# PID.net
KiCad netlist of a schematic drawn in EasyEDA Pro
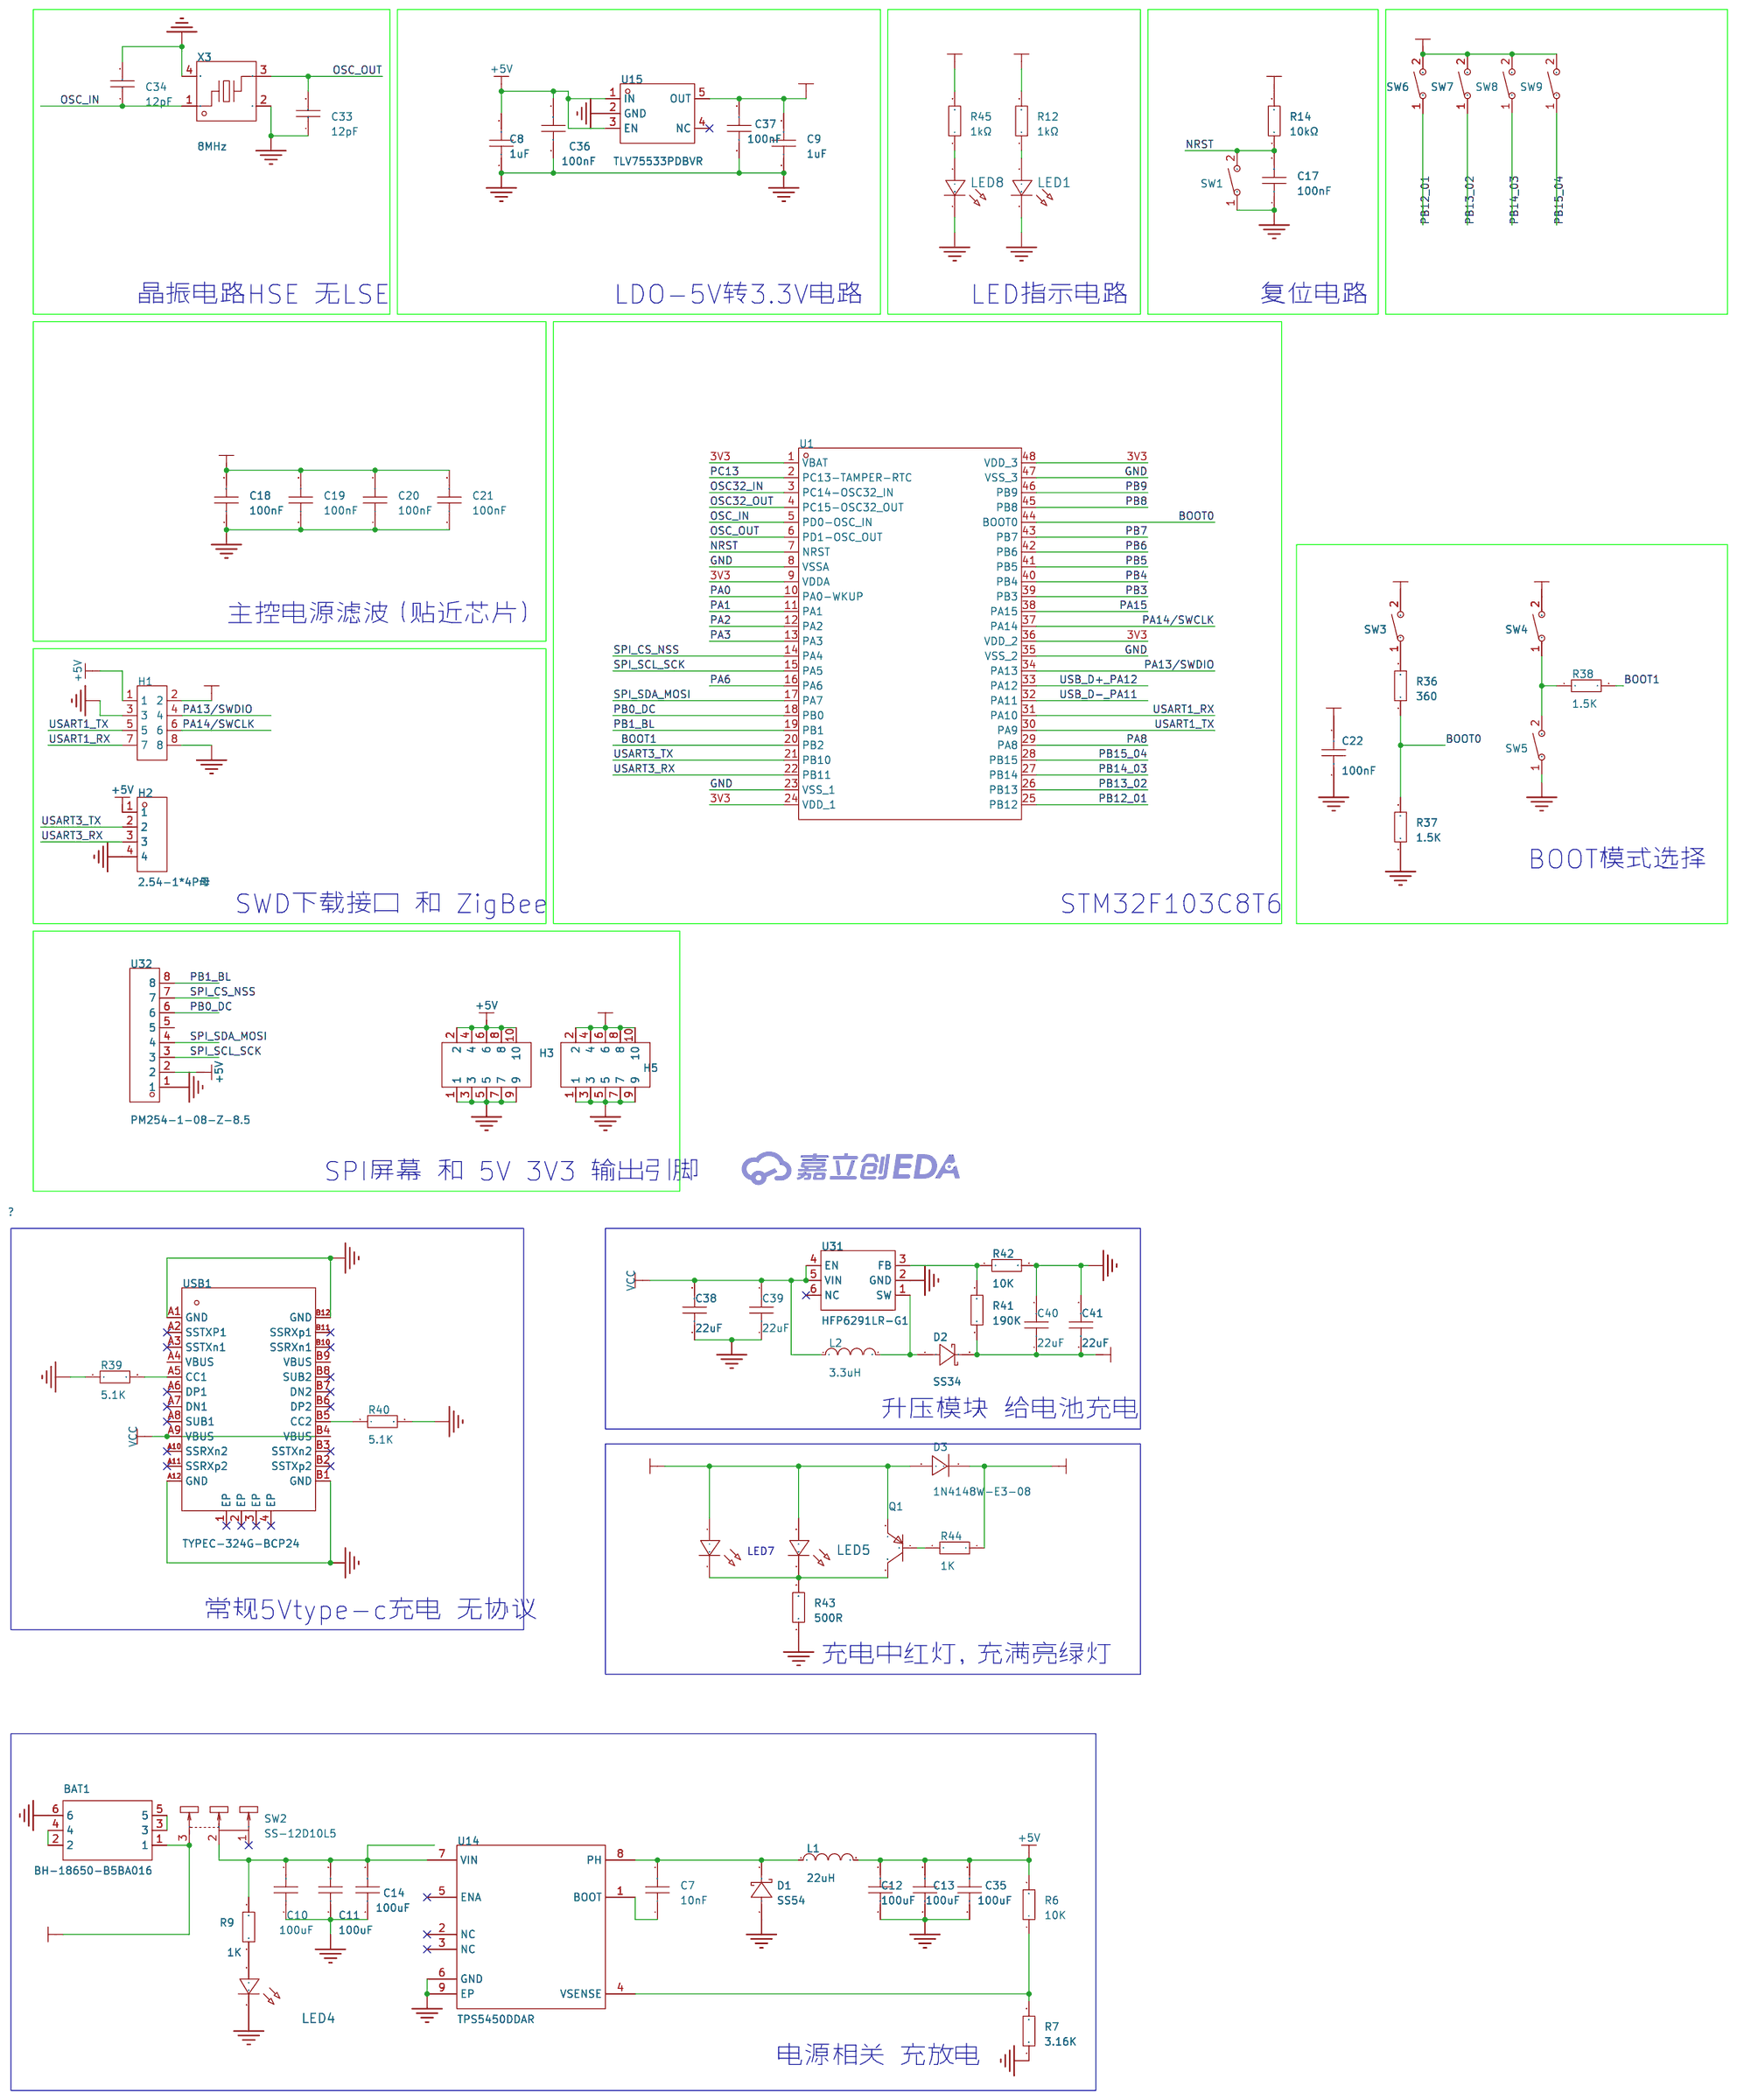
[diagram p0: schematic sheet]

(export (version "E")
  (design (tool "Eeschema 10.0.6"))
  (components
    (comp (ref "BAT1")
      (value "BH-18650-B5BA016")
      (footprint "easyedapro:BAT-SMD_BH-18650-B5BA016")
      (description "连接器类型:电池盒;适用电池规格:-;触点电镀:金;工作温度范围:-25°C~+85°C;")
      (fields (field (name "Manufacturer") "MYOUNG(美阳)"))
      (libsource (lib "easyedapro") (part "BH-18650-B5BA016"))
    )
    (comp (ref "C7")
      (value "100nF")
      (footprint "easyedapro:C0603")
      (libsource (lib "easyedapro") (part "CapAcitance"))
    )
    (comp (ref "C8")
      (value "100nF")
      (footprint "easyedapro:C0603")
      (libsource (lib "easyedapro") (part "CapAcitance"))
    )
    (comp (ref "C9")
      (value "100nF")
      (footprint "easyedapro:C0603")
      (libsource (lib "easyedapro") (part "CapAcitance"))
    )
    (comp (ref "C10")
      (value "100uF")
      (footprint "easyedapro:C1206")
      (description "容值:100uF;精度:±20%;额定电压:10V;材质(温度系数):X5R;")
      (fields
        (field (name "Manufacturer Part") "HGC1206R5107M100NSPJ")
        (field (name "Manufacturer") "Chinocera(华瓷)")
      )
      (libsource (lib "easyedapro") (part "HGC1206R5107M100NSPJ"))
    )
    (comp (ref "C11")
      (value "100uF")
      (footprint "easyedapro:C1206")
      (description "容值:100uF;精度:±20%;额定电压:10V;材质(温度系数):X5R;")
      (fields
        (field (name "Manufacturer Part") "HGC1206R5107M100NSPJ")
        (field (name "Manufacturer") "Chinocera(华瓷)")
      )
      (libsource (lib "easyedapro") (part "HGC1206R5107M100NSPJ"))
    )
    (comp (ref "C12")
      (value "100uF")
      (footprint "easyedapro:C1206")
      (description "容值:100uF;精度:±20%;额定电压:10V;材质(温度系数):X5R;")
      (fields
        (field (name "Manufacturer Part") "HGC1206R5107M100NSPJ")
        (field (name "Manufacturer") "Chinocera(华瓷)")
      )
      (libsource (lib "easyedapro") (part "HGC1206R5107M100NSPJ"))
    )
    (comp (ref "C13")
      (value "100uF")
      (footprint "easyedapro:C1206")
      (description "容值:100uF;精度:±20%;额定电压:10V;材质(温度系数):X5R;")
      (fields
        (field (name "Manufacturer Part") "HGC1206R5107M100NSPJ")
        (field (name "Manufacturer") "Chinocera(华瓷)")
      )
      (libsource (lib "easyedapro") (part "HGC1206R5107M100NSPJ"))
    )
    (comp (ref "C14")
      (value "100uF")
      (footprint "easyedapro:C1206")
      (description "容值:100uF;精度:±20%;额定电压:10V;材质(温度系数):X5R;")
      (fields
        (field (name "Manufacturer Part") "HGC1206R5107M100NSPJ")
        (field (name "Manufacturer") "Chinocera(华瓷)")
      )
      (libsource (lib "easyedapro") (part "HGC1206R5107M100NSPJ"))
    )
    (comp (ref "C17")
      (value "100nF")
      (footprint "easyedapro:C0402")
      (description "容值:100nF;精度:±10%;额定电压:50V;材质(温度系数):X7R;")
      (fields
        (field (name "Manufacturer Part") "GRM155R71H104KE14D")
        (field (name "Manufacturer") "muRata(村田)")
      )
      (libsource (lib "easyedapro") (part "GRM155R71H104KE14D"))
    )
    (comp (ref "C18")
      (value "100nF")
      (footprint "easyedapro:C0402")
      (description "容值:100nF;精度:±10%;额定电压:50V;材质(温度系数):X7R;")
      (fields
        (field (name "Manufacturer Part") "GRM155R71H104KE14D")
        (field (name "Manufacturer") "muRata(村田)")
      )
      (libsource (lib "easyedapro") (part "GRM155R71H104KE14D"))
    )
    (comp (ref "C19")
      (value "100nF")
      (footprint "easyedapro:C0402")
      (description "容值:100nF;精度:±10%;额定电压:50V;材质(温度系数):X7R;")
      (fields
        (field (name "Manufacturer Part") "GRM155R71H104KE14D")
        (field (name "Manufacturer") "muRata(村田)")
      )
      (libsource (lib "easyedapro") (part "GRM155R71H104KE14D"))
    )
    (comp (ref "C20")
      (value "100nF")
      (footprint "easyedapro:C0402")
      (description "容值:100nF;精度:±10%;额定电压:50V;材质(温度系数):X7R;")
      (fields
        (field (name "Manufacturer Part") "GRM155R71H104KE14D")
        (field (name "Manufacturer") "muRata(村田)")
      )
      (libsource (lib "easyedapro") (part "GRM155R71H104KE14D"))
    )
    (comp (ref "C21")
      (value "100nF")
      (footprint "easyedapro:C0402")
      (description "容值:100nF;精度:±10%;额定电压:50V;材质(温度系数):X7R;")
      (fields
        (field (name "Manufacturer Part") "GRM155R71H104KE14D")
        (field (name "Manufacturer") "muRata(村田)")
      )
      (libsource (lib "easyedapro") (part "GRM155R71H104KE14D"))
    )
    (comp (ref "C22")
      (value "100nF")
      (footprint "easyedapro:C0402")
      (description "容值:100nF;精度:±10%;额定电压:50V;材质(温度系数):X7R;")
      (fields
        (field (name "Manufacturer Part") "GRM155R71H104KE14D")
        (field (name "Manufacturer") "muRata(村田)")
      )
      (libsource (lib "easyedapro") (part "GRM155R71H104KE14D"))
    )
    (comp (ref "C33")
      (value "12pF")
      (footprint "easyedapro:C0402")
      (description "容值:12pF;精度:±5%;额定电压:50V;材质(温度系数):C0G;")
      (fields (field (name "Manufacturer Part") "0402CG120J500NT") (field (name "Manufacturer") "FH(风华)"))
      (libsource (lib "easyedapro") (part "0402CG120J500NT"))
    )
    (comp (ref "C34")
      (value "12pF")
      (footprint "easyedapro:C0402")
      (description "容值:12pF;精度:±5%;额定电压:50V;材质(温度系数):C0G;")
      (fields (field (name "Manufacturer Part") "0402CG120J500NT") (field (name "Manufacturer") "FH(风华)"))
      (libsource (lib "easyedapro") (part "0402CG120J500NT"))
    )
    (comp (ref "C35")
      (value "100uF")
      (footprint "easyedapro:C1206")
      (description "容值:100uF;精度:±20%;额定电压:10V;材质(温度系数):X5R;")
      (fields
        (field (name "Manufacturer Part") "HGC1206R5107M100NSPJ")
        (field (name "Manufacturer") "Chinocera(华瓷)")
      )
      (libsource (lib "easyedapro") (part "HGC1206R5107M100NSPJ"))
    )
    (comp (ref "C36")
      (value "100nF")
      (footprint "easyedapro:C0402")
      (description "容值:100nF;精度:±10%;额定电压:50V;材质(温度系数):X7R;")
      (fields
        (field (name "Manufacturer Part") "GRM155R71H104KE14D")
        (field (name "Manufacturer") "muRata(村田)")
      )
      (libsource (lib "easyedapro") (part "GRM155R71H104KE14D"))
    )
    (comp (ref "C37")
      (value "100nF")
      (footprint "easyedapro:C0402")
      (description "容值:100nF;精度:±10%;额定电压:50V;材质(温度系数):X7R;")
      (fields
        (field (name "Manufacturer Part") "GRM155R71H104KE14D")
        (field (name "Manufacturer") "muRata(村田)")
      )
      (libsource (lib "easyedapro") (part "GRM155R71H104KE14D"))
    )
    (comp (ref "C38")
      (value "22uF")
      (footprint "easyedapro:C0603")
      (libsource (lib "easyedapro") (part "CapAcitance"))
    )
    (comp (ref "C39")
      (value "22uF")
      (footprint "easyedapro:C0603")
      (libsource (lib "easyedapro") (part "CapAcitance"))
    )
    (comp (ref "C40")
      (value "22uF")
      (footprint "easyedapro:C0603")
      (libsource (lib "easyedapro") (part "CapAcitance"))
    )
    (comp (ref "C41")
      (value "22uF")
      (footprint "easyedapro:C0603")
      (libsource (lib "easyedapro") (part "CapAcitance"))
    )
    (comp (ref "D1")
      (value "SS54")
      (footprint "easyedapro:SMA_L4.3-W2.6-LS5.0-FD")
      (description "二极管配置:独立式;正向压降(Vf):550mV@5.0A;直流反向耐压(Vr):40V;整流电流:5A;")
      (fields (field (name "Manufacturer") "宏迦橙"))
      (libsource (lib "easyedapro") (part "SS54_C7420369"))
    )
    (comp (ref "D2")
      (value "SS34")
      (footprint "easyedapro:SMA_L4.3-W2.6-LS5.0-FD")
      (description "二极管配置:独立式;正向压降(Vf):550mV@3.0A;直流反向耐压(Vr):40V;整流电流:3A;")
      (fields (field (name "Manufacturer") "宏嘉诚"))
      (libsource (lib "easyedapro") (part "SS34_C7420365"))
    )
    (comp (ref "D3")
      (value "1N4148W-E3-08")
      (footprint "easyedapro:SOD-123_L2.8-W1.8-LS3.7-RD")
      (description "二极管配置:1个独立式;正向压降(Vf):1.2V@100mA;直流反向耐压(Vr):75V;整流电流:150mA;反向恢复时间(Trr):4ns;")
      (fields (field (name "Manufacturer") "VISHAY(威世)"))
      (libsource (lib "easyedapro") (part "1N4148W-E3-08"))
    )
    (comp (ref "H1")
      (value "HX PZ2.54-4x2P ZZ")
      (footprint "easyedapro:HDR-TH_8P-P2.54-V-M-R2-C4-S2.54")
      (fields (field (name "Manufacturer") "hanxia(韩下)"))
      (libsource (lib "easyedapro") (part "HX PZ2.54-4X2P ZZ"))
    )
    (comp (ref "H2")
      (value "2.54-1*4P母")
      (footprint "easyedapro:HDR-TH_4P-P2.54-V-F")
      (fields (field (name "Manufacturer") "BOOMELE(博穆精密)"))
      (libsource (lib "easyedapro") (part "2.54-1*4P母"))
    )
    (comp (ref "H3")
      (value "PZ254V-12-10P")
      (footprint "easyedapro:HDR-TH_10P-P2.54-V-M-R2-C5-S2.54")
      (fields (field (name "Manufacturer") "XFCN(兴飞)"))
      (libsource (lib "easyedapro") (part "PZ254V-12-10P"))
    )
    (comp (ref "H5")
      (value "PZ254V-12-10P")
      (footprint "easyedapro:HDR-TH_10P-P2.54-V-M-R2-C5-S2.54")
      (fields (field (name "Manufacturer") "XFCN(兴飞)"))
      (libsource (lib "easyedapro") (part "PZ254V-12-10P"))
    )
    (comp (ref "L1")
      (value "22uH")
      (footprint "easyedapro:IND-SMD_L7.1-W6.6")
      (description "电感值:22uH;精度:±20%;额定电流:3A;")
      (fields
        (field (name "Manufacturer Part") "YSPI0630A-220M")
        (field (name "Manufacturer") "YJYCOIN(益嘉源)")
      )
      (libsource (lib "easyedapro") (part "YSPI0630A-220M"))
    )
    (comp (ref "L2")
      (value "3.3uH")
      (footprint "easyedapro:IND-SMD_L4.4-W4.2-A")
      (description "电感值:3.3uH;精度:±20%;额定电流:3.3A;饱和电流(Isat):4A;类型:一体成型电感;")
      (fields (field (name "Manufacturer Part") "FXL0420-3R3-M") (field (name "Manufacturer") "cjiang(长江微电)"))
      (libsource (lib "easyedapro") (part "FXL0420-3R3-M"))
    )
    (comp (ref "LED1")
      (value "LTST-C190KSKT")
      (footprint "easyedapro:LED_0603")
      (fields (field (name "Manufacturer") "LITEON(光宝)"))
      (libsource (lib "easyedapro") (part "LED_R"))
    )
    (comp (ref "LED4")
      (value "~")
      (footprint "easyedapro:LED_0603")
      (libsource (lib "easyedapro") (part "LED_R"))
    )
    (comp (ref "LED5")
      (value "~")
      (footprint "easyedapro:LED_0603")
      (libsource (lib "easyedapro") (part "LED_R"))
    )
    (comp (ref "LED7")
      (value "~")
      (footprint "easyedapro:LED_0603")
      (libsource (lib "easyedapro") (part "LED_G"))
    )
    (comp (ref "LED8")
      (value "LTST-C190KSKT")
      (footprint "easyedapro:LED_0603")
      (fields (field (name "Manufacturer") "LITEON(光宝)"))
      (libsource (lib "easyedapro") (part "LED_R"))
    )
    (comp (ref "Q1")
      (value "~")
      (footprint "easyedapro:S8550P_SOT")
      (libsource (lib "easyedapro") (part "PNP"))
    )
    (comp (ref "R6") (value "10K") (footprint "easyedapro:R0603") (libsource (lib "easyedapro") (part "电阻")))
    (comp (ref "R7") (value "10K") (footprint "easyedapro:R0603") (libsource (lib "easyedapro") (part "电阻")))
    (comp (ref "R9") (value "1K") (footprint "easyedapro:R0603") (libsource (lib "easyedapro") (part "电阻")))
    (comp (ref "R12")
      (value "1kΩ")
      (footprint "easyedapro:R0402")
      (description "电阻类型:厚膜电阻;阻值:1kΩ;精度:±1%;功率:62.5mW;最大工作电压:50V;温度系数:±100ppm/°C;")
      (fields
        (field (name "Manufacturer Part") "0402WGF1001TCE")
        (field (name "Manufacturer") "UNI-ROYAL(厚声)")
      )
      (libsource (lib "easyedapro") (part "0402WGF1001TCE"))
    )
    (comp (ref "R14")
      (value "10kΩ")
      (footprint "easyedapro:R0402")
      (description "电阻类型:厚膜电阻;阻值:10kΩ;精度:±1%;功率:62.5mW;最大工作电压:50V;温度系数:±100ppm/°C;")
      (fields (field (name "Manufacturer Part") "RC0402FR-0710KL") (field (name "Manufacturer") "YAGEO(国巨)"))
      (libsource (lib "easyedapro") (part "RC0402FR-0710KL"))
    )
    (comp (ref "R36") (value "360") (footprint "easyedapro:R0603") (libsource (lib "easyedapro") (part "电阻")))
    (comp (ref "R37")
      (value "1.5K")
      (footprint "easyedapro:R0603")
      (libsource (lib "easyedapro") (part "电阻"))
    )
    (comp (ref "R38")
      (value "1.5K")
      (footprint "easyedapro:R0603")
      (libsource (lib "easyedapro") (part "电阻"))
    )
    (comp (ref "R39")
      (value "5.1K")
      (footprint "easyedapro:R0603")
      (libsource (lib "easyedapro") (part "电阻"))
    )
    (comp (ref "R40")
      (value "5.1K")
      (footprint "easyedapro:R0603")
      (libsource (lib "easyedapro") (part "电阻"))
    )
    (comp (ref "R41")
      (value "190K")
      (footprint "easyedapro:R0603")
      (libsource (lib "easyedapro") (part "电阻"))
    )
    (comp (ref "R42") (value "10K") (footprint "easyedapro:R0603") (libsource (lib "easyedapro") (part "电阻")))
    (comp (ref "R43")
      (value "500R")
      (footprint "easyedapro:R0603")
      (libsource (lib "easyedapro") (part "电阻"))
    )
    (comp (ref "R44") (value "1K") (footprint "easyedapro:R0603") (libsource (lib "easyedapro") (part "电阻")))
    (comp (ref "R45")
      (value "1kΩ")
      (footprint "easyedapro:R0402")
      (description "电阻类型:厚膜电阻;阻值:1kΩ;精度:±1%;功率:62.5mW;最大工作电压:50V;温度系数:±100ppm/°C;")
      (fields
        (field (name "Manufacturer Part") "0402WGF1001TCE")
        (field (name "Manufacturer") "UNI-ROYAL(厚声)")
      )
      (libsource (lib "easyedapro") (part "0402WGF1001TCE"))
    )
    (comp (ref "SW1")
      (value "TS-1101-B-W")
      (footprint "easyedapro:KEY-SMD_2P-L6.0-W3.6-P7.4-LS8.0-L")
      (description "触点电流:50mA;额定电压(DC):12V;绝缘电阻:-;电路结构:单刀单掷;安装方式:立贴;带灯:无;作用力:160gf;机械寿命:5万次;带支架:否;")
      (fields (field (name "Manufacturer") "XKB Connectivity(中国星坤)"))
      (libsource (lib "easyedapro") (part "TS-1101-B-W"))
    )
    (comp (ref "SW2")
      (value "SS-12D10L5")
      (footprint "easyedapro:SW-TH_SS-12D10L5")
      (description "电路结构:单刀双掷;安装方式:直插;开关颜色:黑色;额定电流(DC):3A;额定电压(DC):125V;额定电流(AC):3A;额定电压(AC):125V;机械寿命:1万次;")
      (fields (field (name "Manufacturer") "XKB Connectivity(中国星坤)"))
      (libsource (lib "easyedapro") (part "SS-12D10L5"))
    )
    (comp (ref "SW3")
      (value "TS-1101-B-W")
      (footprint "easyedapro:KEY-SMD_2P-L6.0-W3.6-P7.4-LS8.0-L")
      (description "触点电流:50mA;额定电压(DC):12V;绝缘电阻:-;电路结构:单刀单掷;安装方式:立贴;带灯:无;作用力:160gf;机械寿命:5万次;带支架:否;")
      (fields (field (name "Manufacturer") "XKB Connectivity(中国星坤)"))
      (libsource (lib "easyedapro") (part "TS-1101-B-W"))
    )
    (comp (ref "SW4")
      (value "TS-1101-B-W")
      (footprint "easyedapro:KEY-SMD_2P-L6.0-W3.6-P7.4-LS8.0-L")
      (description "触点电流:50mA;额定电压(DC):12V;绝缘电阻:-;电路结构:单刀单掷;安装方式:立贴;带灯:无;作用力:160gf;机械寿命:5万次;带支架:否;")
      (fields (field (name "Manufacturer") "XKB Connectivity(中国星坤)"))
      (libsource (lib "easyedapro") (part "TS-1101-B-W"))
    )
    (comp (ref "SW5")
      (value "TS-1101-B-W")
      (footprint "easyedapro:KEY-SMD_2P-L6.0-W3.6-P7.4-LS8.0-L")
      (description "触点电流:50mA;额定电压(DC):12V;绝缘电阻:-;电路结构:单刀单掷;安装方式:立贴;带灯:无;作用力:160gf;机械寿命:5万次;带支架:否;")
      (fields (field (name "Manufacturer") "XKB Connectivity(中国星坤)"))
      (libsource (lib "easyedapro") (part "TS-1101-B-W"))
    )
    (comp (ref "SW6")
      (value "TS-1101-B-W")
      (footprint "easyedapro:KEY-SMD_2P-L6.0-W3.6-P7.4-LS8.0-L")
      (description "触点电流:50mA;额定电压(DC):12V;绝缘电阻:-;电路结构:单刀单掷;安装方式:立贴;带灯:无;作用力:160gf;机械寿命:5万次;带支架:否;")
      (fields (field (name "Manufacturer") "XKB Connectivity(中国星坤)"))
      (libsource (lib "easyedapro") (part "TS-1101-B-W"))
    )
    (comp (ref "SW7")
      (value "TS-1101-B-W")
      (footprint "easyedapro:KEY-SMD_2P-L6.0-W3.6-P7.4-LS8.0-L")
      (description "触点电流:50mA;额定电压(DC):12V;绝缘电阻:-;电路结构:单刀单掷;安装方式:立贴;带灯:无;作用力:160gf;机械寿命:5万次;带支架:否;")
      (fields (field (name "Manufacturer") "XKB Connectivity(中国星坤)"))
      (libsource (lib "easyedapro") (part "TS-1101-B-W"))
    )
    (comp (ref "SW8")
      (value "TS-1101-B-W")
      (footprint "easyedapro:KEY-SMD_2P-L6.0-W3.6-P7.4-LS8.0-L")
      (description "触点电流:50mA;额定电压(DC):12V;绝缘电阻:-;电路结构:单刀单掷;安装方式:立贴;带灯:无;作用力:160gf;机械寿命:5万次;带支架:否;")
      (fields (field (name "Manufacturer") "XKB Connectivity(中国星坤)"))
      (libsource (lib "easyedapro") (part "TS-1101-B-W"))
    )
    (comp (ref "SW9")
      (value "TS-1101-B-W")
      (footprint "easyedapro:KEY-SMD_2P-L6.0-W3.6-P7.4-LS8.0-L")
      (description "触点电流:50mA;额定电压(DC):12V;绝缘电阻:-;电路结构:单刀单掷;安装方式:立贴;带灯:无;作用力:160gf;机械寿命:5万次;带支架:否;")
      (fields (field (name "Manufacturer") "XKB Connectivity(中国星坤)"))
      (libsource (lib "easyedapro") (part "TS-1101-B-W"))
    )
    (comp (ref "U1")
      (value "STM32F103C8T6")
      (footprint "easyedapro:LQFP-48_L7.0-W7.0-P0.50-LS9.0-BL")
      (description "CPU内核:CM3;程序存储容量:64KB;RAM总容量:20KB;GPIO端口数量:37;工作电压范围:2V~3.6V;CPU最大主频:72MHz;程序存储器类型:FLASH;")
      (fields (field (name "Manufacturer") "ST(意法半导体)"))
      (libsource (lib "easyedapro") (part "STM32F103C8T6"))
    )
    (comp (ref "U14")
      (value "TPS5450DDAR")
      (footprint "easyedapro:SOP-8_L4.9-W3.9-P1.27-LS6.0-BL-EP")
      (description "功能类型:降压型;输出类型:可调;工作电压:5.5V~36V;输出电压:1.221V~31.32V;输出电流:5A;")
      (fields (field (name "Manufacturer") "TI(德州仪器)"))
      (libsource (lib "easyedapro") (part "TPS5450DDAR"))
    )
    (comp (ref "U15")
      (value "TLV75533PDBVR")
      (footprint "easyedapro:SOT-23-5_L3.0-W1.7-P0.95-LS2.8-BR")
      (description "输出类型:固定;最大输入电压:5.5V;输出电压:3.3V;输出电流:500mA;电源纹波抑制比(PSRR):52dB;输出极性:正极;")
      (fields (field (name "Manufacturer") "TI(德州仪器)"))
      (libsource (lib "easyedapro") (part "TLV75533PDBVR"))
    )
    (comp (ref "U31")
      (value "HFP6291LR-G1")
      (footprint "easyedapro:SOT-23-6_L2.9-W1.6-P0.95-LS2.8-BR")
      (description "功能类型:升压型;输出类型:-;工作电压:2V~24V;输出电压:-;输出电流:-;")
      (fields (field (name "Manufacturer") "HXY MOSFET(华轩阳电子)"))
      (libsource (lib "easyedapro") (part "HFP6291LR-G1"))
    )
    (comp (ref "U32")
      (value "PM254-1-08-Z-8.5")
      (footprint "easyedapro:HDR-TH_8P-P2.54-V-F")
      (fields (field (name "Manufacturer") "HCTL(华灿天禄)"))
      (libsource (lib "easyedapro") (part "PM254-1-08-Z-8.5"))
    )
    (comp (ref "USB1")
      (value "TYPEC-324G-BCP24")
      (footprint "easyedapro:USB-C-SMD_TYPEC-324G-BCP24")
      (description "连接器类型:Type-C;标准:USB 3.1;公母:母;安装方式:卧贴;触点数量:24P;端口数量:1;额定电流 - 电源:5A;工作温度范围:-45°C~+85°C;")
      (fields (field (name "Manufacturer") "XUNPU(讯普)"))
      (libsource (lib "easyedapro") (part "TYPEC-324G-BCP24"))
    )
    (comp (ref "X3")
      (value "8MHz")
      (footprint "easyedapro:CRYSTAL-SMD_4P-L3.2-W2.5-BL-1")
      (description "晶振类型:贴片晶振;频率:8MHz;常温频差:±10ppm;外接负载电容:12pF;频率稳定度(全温):±20ppm;")
      (fields
        (field (name "Manufacturer Part") "XL2EL89COI-111YLC-8M")
        (field (name "Manufacturer") "YXC(扬兴晶振)")
      )
      (libsource (lib "easyedapro") (part "XL2EL89COI-111YLC-8M"))
    )
  )
  (nets
    (net (code "1") (name "+5V") (class "Default")
      (node (ref "C12") (pin "2") (pinfunction "2_2") (pintype "unspecified"))
      (node (ref "C13") (pin "2") (pinfunction "2_2") (pintype "unspecified"))
      (node (ref "C35") (pin "2") (pinfunction "2_2") (pintype "unspecified"))
      (node (ref "C36") (pin "2") (pinfunction "2_2") (pintype "unspecified"))
      (node (ref "C8") (pin "2") (pinfunction "2_2") (pintype "input"))
      (node (ref "H1") (pin "1") (pinfunction "1_1") (pintype "unspecified"))
      (node (ref "H2") (pin "1") (pinfunction "1_1") (pintype "unspecified"))
      (node (ref "H3") (pin "10") (pinfunction "10_10") (pintype "unspecified"))
      (node (ref "H3") (pin "2") (pinfunction "2_2") (pintype "unspecified"))
      (node (ref "H3") (pin "4") (pinfunction "4_4") (pintype "unspecified"))
      (node (ref "H3") (pin "6") (pinfunction "6_6") (pintype "unspecified"))
      (node (ref "H3") (pin "8") (pinfunction "8_8") (pintype "unspecified"))
      (node (ref "L1") (pin "2") (pinfunction "2_2") (pintype "unspecified"))
      (node (ref "R45") (pin "2") (pinfunction "2_2") (pintype "input"))
      (node (ref "R6") (pin "2") (pinfunction "2_2") (pintype "input"))
      (node (ref "U15") (pin "1") (pinfunction "IN_1") (pintype "unspecified"))
      (node (ref "U15") (pin "3") (pinfunction "EN_3") (pintype "unspecified"))
      (node (ref "U32") (pin "2") (pinfunction "2_2") (pintype "unspecified"))
    )
    (net (code "2") (name "+12V") (class "Default")
      (node (ref "C40") (pin "1") (pinfunction "1_1") (pintype "input"))
      (node (ref "C41") (pin "1") (pinfunction "1_1") (pintype "input"))
      (node (ref "D2") (pin "2") (pinfunction "K_2") (pintype "unspecified"))
      (node (ref "D3") (pin "2") (pinfunction "A_2") (pintype "unspecified"))
      (node (ref "LED5") (pin "2") (pinfunction "A_2") (pintype "input"))
      (node (ref "LED7") (pin "2") (pinfunction "A_2") (pintype "input"))
      (node (ref "Q1") (pin "2") (pinfunction "E_2") (pintype "input"))
      (node (ref "R41") (pin "1") (pinfunction "1_1") (pintype "input"))
    )
    (net (code "3") (name "/BOOT0") (class "Default")
      (node (ref "R36") (pin "1") (pinfunction "1_1") (pintype "input"))
      (node (ref "R37") (pin "2") (pinfunction "2_2") (pintype "input"))
      (node (ref "U1") (pin "44") (pinfunction "BOOT0_44") (pintype "unspecified"))
    )
    (net (code "4") (name "/BOOT1") (class "Default")
      (node (ref "R38") (pin "2") (pinfunction "2_2") (pintype "input"))
      (node (ref "U1") (pin "20") (pinfunction "PB2_20") (pintype "unspecified"))
    )
    (net (code "5") (name "/NRST") (class "Default")
      (node (ref "C17") (pin "2") (pinfunction "2_2") (pintype "unspecified"))
      (node (ref "R14") (pin "1") (pinfunction "1_1") (pintype "input"))
      (node (ref "SW1") (pin "2") (pinfunction "2_2") (pintype "input"))
      (node (ref "U1") (pin "7") (pinfunction "NRST_7") (pintype "unspecified"))
    )
    (net (code "6") (name "/OSC32_IN") (class "Default")
      (node (ref "U1") (pin "3") (pinfunction "PC14-OSC32_IN_3") (pintype "unspecified"))
    )
    (net (code "7") (name "/OSC32_OUT") (class "Default")
      (node (ref "U1") (pin "4") (pinfunction "PC15-OSC32_OUT_4") (pintype "unspecified"))
    )
    (net (code "8") (name "/OSC_IN") (class "Default")
      (node (ref "C34") (pin "1") (pinfunction "1_1") (pintype "input"))
      (node (ref "U1") (pin "5") (pinfunction "PD0-OSC_IN_5") (pintype "unspecified"))
      (node (ref "X3") (pin "1") (pinfunction "1_1") (pintype "input"))
    )
    (net (code "9") (name "/OSC_OUT") (class "Default")
      (node (ref "C33") (pin "2") (pinfunction "2_2") (pintype "input"))
      (node (ref "U1") (pin "6") (pinfunction "PD1-OSC_OUT_6") (pintype "unspecified"))
      (node (ref "X3") (pin "3") (pinfunction "3_3") (pintype "input"))
    )
    (net (code "10") (name "/PA0") (class "Default")
      (node (ref "U1") (pin "10") (pinfunction "PA0-WKUP_10") (pintype "unspecified"))
    )
    (net (code "11") (name "/PA1") (class "Default")
      (node (ref "U1") (pin "11") (pinfunction "PA1_11") (pintype "unspecified"))
    )
    (net (code "12") (name "/PA2") (class "Default")
      (node (ref "U1") (pin "12") (pinfunction "PA2_12") (pintype "unspecified"))
    )
    (net (code "13") (name "/PA3") (class "Default")
      (node (ref "U1") (pin "13") (pinfunction "PA3_13") (pintype "unspecified"))
    )
    (net (code "14") (name "/PA6") (class "Default")
      (node (ref "U1") (pin "16") (pinfunction "PA6_16") (pintype "unspecified"))
    )
    (net (code "15") (name "/PA8") (class "Default")
      (node (ref "U1") (pin "29") (pinfunction "PA8_29") (pintype "unspecified"))
    )
    (net (code "16") (name "/PA13{slash}SWDIO") (class "Default")
      (node (ref "H1") (pin "4") (pinfunction "4_4") (pintype "unspecified"))
      (node (ref "U1") (pin "34") (pinfunction "PA13_34") (pintype "unspecified"))
    )
    (net (code "17") (name "/PA14{slash}SWCLK") (class "Default")
      (node (ref "H1") (pin "6") (pinfunction "6_6") (pintype "unspecified"))
      (node (ref "U1") (pin "37") (pinfunction "PA14_37") (pintype "unspecified"))
    )
    (net (code "18") (name "/PA15") (class "Default")
      (node (ref "U1") (pin "38") (pinfunction "PA15_38") (pintype "unspecified"))
    )
    (net (code "19") (name "/PB0_DC") (class "Default")
      (node (ref "U1") (pin "18") (pinfunction "PB0_18") (pintype "unspecified"))
      (node (ref "U32") (pin "6") (pinfunction "6_6") (pintype "unspecified"))
    )
    (net (code "20") (name "/PB1_BL") (class "Default")
      (node (ref "U1") (pin "19") (pinfunction "PB1_19") (pintype "unspecified"))
      (node (ref "U32") (pin "8") (pinfunction "8_8") (pintype "unspecified"))
    )
    (net (code "21") (name "/PB3") (class "Default")
      (node (ref "U1") (pin "39") (pinfunction "PB3_39") (pintype "unspecified"))
    )
    (net (code "22") (name "/PB4") (class "Default")
      (node (ref "U1") (pin "40") (pinfunction "PB4_40") (pintype "unspecified"))
    )
    (net (code "23") (name "/PB5") (class "Default")
      (node (ref "U1") (pin "41") (pinfunction "PB5_41") (pintype "unspecified"))
    )
    (net (code "24") (name "/PB6") (class "Default")
      (node (ref "U1") (pin "42") (pinfunction "PB6_42") (pintype "unspecified"))
    )
    (net (code "25") (name "/PB7") (class "Default")
      (node (ref "U1") (pin "43") (pinfunction "PB7_43") (pintype "unspecified"))
    )
    (net (code "26") (name "/PB8") (class "Default")
      (node (ref "U1") (pin "45") (pinfunction "PB8_45") (pintype "unspecified"))
    )
    (net (code "27") (name "/PB9") (class "Default")
      (node (ref "U1") (pin "46") (pinfunction "PB9_46") (pintype "unspecified"))
    )
    (net (code "28") (name "/PB12_01") (class "Default")
      (node (ref "SW6") (pin "1") (pinfunction "1_1") (pintype "input"))
      (node (ref "U1") (pin "25") (pinfunction "PB12_25") (pintype "unspecified"))
    )
    (net (code "29") (name "/PB13_02") (class "Default")
      (node (ref "SW7") (pin "1") (pinfunction "1_1") (pintype "input"))
      (node (ref "U1") (pin "26") (pinfunction "PB13_26") (pintype "unspecified"))
    )
    (net (code "30") (name "/PB14_03") (class "Default")
      (node (ref "SW8") (pin "1") (pinfunction "1_1") (pintype "input"))
      (node (ref "U1") (pin "27") (pinfunction "PB14_27") (pintype "unspecified"))
    )
    (net (code "31") (name "/PB15_04") (class "Default")
      (node (ref "SW9") (pin "1") (pinfunction "1_1") (pintype "input"))
      (node (ref "U1") (pin "28") (pinfunction "PB15_28") (pintype "unspecified"))
    )
    (net (code "32") (name "/PC13") (class "Default")
      (node (ref "U1") (pin "2") (pinfunction "PC13-TAMPER-RTC_2") (pintype "unspecified"))
    )
    (net (code "33") (name "/SPI_CS_NSS") (class "Default")
      (node (ref "U1") (pin "14") (pinfunction "PA4_14") (pintype "unspecified"))
      (node (ref "U32") (pin "7") (pinfunction "7_7") (pintype "unspecified"))
    )
    (net (code "34") (name "/SPI_SCL_SCK") (class "Default")
      (node (ref "U1") (pin "15") (pinfunction "PA5_15") (pintype "unspecified"))
      (node (ref "U32") (pin "3") (pinfunction "3_3") (pintype "unspecified"))
    )
    (net (code "35") (name "/SPI_SDA_MOSI") (class "Default")
      (node (ref "U1") (pin "17") (pinfunction "PA7_17") (pintype "unspecified"))
      (node (ref "U32") (pin "4") (pinfunction "4_4") (pintype "unspecified"))
    )
    (net (code "36") (name "/USART1_RX") (class "Default")
      (node (ref "H1") (pin "7") (pinfunction "7_7") (pintype "unspecified"))
      (node (ref "U1") (pin "31") (pinfunction "PA10_31") (pintype "unspecified"))
    )
    (net (code "37") (name "/USART1_TX") (class "Default")
      (node (ref "H1") (pin "5") (pinfunction "5_5") (pintype "unspecified"))
      (node (ref "U1") (pin "30") (pinfunction "PA9_30") (pintype "unspecified"))
    )
    (net (code "38") (name "/USART3_RX") (class "Default")
      (node (ref "H2") (pin "3") (pinfunction "3_3") (pintype "unspecified"))
      (node (ref "U1") (pin "22") (pinfunction "PB11_22") (pintype "unspecified"))
    )
    (net (code "39") (name "/USART3_TX") (class "Default")
      (node (ref "H2") (pin "2") (pinfunction "2_2") (pintype "unspecified"))
      (node (ref "U1") (pin "21") (pinfunction "PB10_21") (pintype "unspecified"))
    )
    (net (code "40") (name "/USB_D+_PA12") (class "Default")
      (node (ref "U1") (pin "33") (pinfunction "PA12_33") (pintype "unspecified"))
    )
    (net (code "41") (name "/USB_D-_PA11") (class "Default")
      (node (ref "U1") (pin "32") (pinfunction "PA11_32") (pintype "unspecified"))
    )
    (net (code "42") (name "3V3") (class "Default")
      (node (ref "C18") (pin "2") (pinfunction "2_2") (pintype "unspecified"))
      (node (ref "C19") (pin "2") (pinfunction "2_2") (pintype "unspecified"))
      (node (ref "C20") (pin "2") (pinfunction "2_2") (pintype "unspecified"))
      (node (ref "C21") (pin "2") (pinfunction "2_2") (pintype "unspecified"))
      (node (ref "C22") (pin "2") (pinfunction "2_2") (pintype "unspecified"))
      (node (ref "C37") (pin "2") (pinfunction "2_2") (pintype "unspecified"))
      (node (ref "C9") (pin "2") (pinfunction "2_2") (pintype "input"))
      (node (ref "H1") (pin "2") (pinfunction "2_2") (pintype "unspecified"))
      (node (ref "H5") (pin "10") (pinfunction "10_10") (pintype "unspecified"))
      (node (ref "H5") (pin "2") (pinfunction "2_2") (pintype "unspecified"))
      (node (ref "H5") (pin "4") (pinfunction "4_4") (pintype "unspecified"))
      (node (ref "H5") (pin "6") (pinfunction "6_6") (pintype "unspecified"))
      (node (ref "H5") (pin "8") (pinfunction "8_8") (pintype "unspecified"))
      (node (ref "R12") (pin "2") (pinfunction "2_2") (pintype "input"))
      (node (ref "R14") (pin "2") (pinfunction "2_2") (pintype "input"))
      (node (ref "SW3") (pin "2") (pinfunction "2_2") (pintype "input"))
      (node (ref "SW4") (pin "2") (pinfunction "2_2") (pintype "input"))
      (node (ref "SW6") (pin "2") (pinfunction "2_2") (pintype "input"))
      (node (ref "SW7") (pin "2") (pinfunction "2_2") (pintype "input"))
      (node (ref "SW8") (pin "2") (pinfunction "2_2") (pintype "input"))
      (node (ref "SW9") (pin "2") (pinfunction "2_2") (pintype "input"))
      (node (ref "U1") (pin "1") (pinfunction "VBAT_1") (pintype "unspecified"))
      (node (ref "U1") (pin "24") (pinfunction "VDD_1_24") (pintype "unspecified"))
      (node (ref "U1") (pin "36") (pinfunction "VDD_2_36") (pintype "unspecified"))
      (node (ref "U1") (pin "48") (pinfunction "VDD_3_48") (pintype "unspecified"))
      (node (ref "U1") (pin "9") (pinfunction "VDDA_9") (pintype "unspecified"))
      (node (ref "U15") (pin "5") (pinfunction "OUT_5") (pintype "unspecified"))
    )
    (net (code "43") (name "GND") (class "Default")
      (node (ref "BAT1") (pin "6") (pinfunction "6_6") (pintype "unspecified"))
      (node (ref "C10") (pin "1") (pinfunction "1_1") (pintype "unspecified"))
      (node (ref "C11") (pin "1") (pinfunction "1_1") (pintype "unspecified"))
      (node (ref "C12") (pin "1") (pinfunction "1_1") (pintype "unspecified"))
      (node (ref "C13") (pin "1") (pinfunction "1_1") (pintype "unspecified"))
      (node (ref "C14") (pin "1") (pinfunction "1_1") (pintype "unspecified"))
      (node (ref "C17") (pin "1") (pinfunction "1_1") (pintype "unspecified"))
      (node (ref "C18") (pin "1") (pinfunction "1_1") (pintype "unspecified"))
      (node (ref "C19") (pin "1") (pinfunction "1_1") (pintype "unspecified"))
      (node (ref "C20") (pin "1") (pinfunction "1_1") (pintype "unspecified"))
      (node (ref "C21") (pin "1") (pinfunction "1_1") (pintype "unspecified"))
      (node (ref "C22") (pin "1") (pinfunction "1_1") (pintype "unspecified"))
      (node (ref "C33") (pin "1") (pinfunction "1_1") (pintype "input"))
      (node (ref "C34") (pin "2") (pinfunction "2_2") (pintype "input"))
      (node (ref "C35") (pin "1") (pinfunction "1_1") (pintype "unspecified"))
      (node (ref "C36") (pin "1") (pinfunction "1_1") (pintype "unspecified"))
      (node (ref "C37") (pin "1") (pinfunction "1_1") (pintype "unspecified"))
      (node (ref "C38") (pin "1") (pinfunction "1_1") (pintype "input"))
      (node (ref "C39") (pin "1") (pinfunction "1_1") (pintype "input"))
      (node (ref "C40") (pin "2") (pinfunction "2_2") (pintype "input"))
      (node (ref "C41") (pin "2") (pinfunction "2_2") (pintype "input"))
      (node (ref "C8") (pin "1") (pinfunction "1_1") (pintype "input"))
      (node (ref "C9") (pin "1") (pinfunction "1_1") (pintype "input"))
      (node (ref "D1") (pin "1") (pinfunction "A_1") (pintype "unspecified"))
      (node (ref "H1") (pin "3") (pinfunction "3_3") (pintype "unspecified"))
      (node (ref "H1") (pin "8") (pinfunction "8_8") (pintype "unspecified"))
      (node (ref "H2") (pin "4") (pinfunction "4_4") (pintype "unspecified"))
      (node (ref "H3") (pin "1") (pinfunction "1_1") (pintype "unspecified"))
      (node (ref "H3") (pin "3") (pinfunction "3_3") (pintype "unspecified"))
      (node (ref "H3") (pin "5") (pinfunction "5_5") (pintype "unspecified"))
      (node (ref "H3") (pin "7") (pinfunction "7_7") (pintype "unspecified"))
      (node (ref "H3") (pin "9") (pinfunction "9_9") (pintype "unspecified"))
      (node (ref "H5") (pin "1") (pinfunction "1_1") (pintype "unspecified"))
      (node (ref "H5") (pin "3") (pinfunction "3_3") (pintype "unspecified"))
      (node (ref "H5") (pin "5") (pinfunction "5_5") (pintype "unspecified"))
      (node (ref "H5") (pin "7") (pinfunction "7_7") (pintype "unspecified"))
      (node (ref "H5") (pin "9") (pinfunction "9_9") (pintype "unspecified"))
      (node (ref "LED1") (pin "1") (pinfunction "C_1") (pintype "input"))
      (node (ref "LED4") (pin "1") (pinfunction "C_1") (pintype "input"))
      (node (ref "LED8") (pin "1") (pinfunction "C_1") (pintype "input"))
      (node (ref "R37") (pin "1") (pinfunction "1_1") (pintype "input"))
      (node (ref "R39") (pin "1") (pinfunction "1_1") (pintype "input"))
      (node (ref "R40") (pin "2") (pinfunction "2_2") (pintype "input"))
      (node (ref "R42") (pin "2") (pinfunction "2_2") (pintype "input"))
      (node (ref "R43") (pin "1") (pinfunction "1_1") (pintype "input"))
      (node (ref "R7") (pin "1") (pinfunction "1_1") (pintype "input"))
      (node (ref "SW1") (pin "1") (pinfunction "1_1") (pintype "input"))
      (node (ref "SW5") (pin "1") (pinfunction "1_1") (pintype "input"))
      (node (ref "U1") (pin "23") (pinfunction "VSS_1_23") (pintype "unspecified"))
      (node (ref "U1") (pin "35") (pinfunction "VSS_2_35") (pintype "unspecified"))
      (node (ref "U1") (pin "47") (pinfunction "VSS_3_47") (pintype "unspecified"))
      (node (ref "U1") (pin "8") (pinfunction "VSSA_8") (pintype "unspecified"))
      (node (ref "U14") (pin "6") (pinfunction "GND_6") (pintype "unspecified"))
      (node (ref "U14") (pin "9") (pinfunction "EP_9") (pintype "unspecified"))
      (node (ref "U15") (pin "2") (pinfunction "GND_2") (pintype "unspecified"))
      (node (ref "U31") (pin "2") (pinfunction "GND_2") (pintype "unspecified"))
      (node (ref "U32") (pin "1") (pinfunction "1_1") (pintype "unspecified"))
      (node (ref "USB1") (pin "A1") (pinfunction "GND_A1") (pintype "unspecified"))
      (node (ref "USB1") (pin "A12") (pinfunction "GND_A12") (pintype "unspecified"))
      (node (ref "USB1") (pin "B1") (pinfunction "GND_B1") (pintype "unspecified"))
      (node (ref "USB1") (pin "B12") (pinfunction "GND_B12") (pintype "unspecified"))
      (node (ref "X3") (pin "2") (pinfunction "GND_2") (pintype "input"))
      (node (ref "X3") (pin "4") (pinfunction "GND_4") (pintype "input"))
    )
    (net (code "44") (name "Net-(BAT1-Pad2)") (class "Default")
      (node (ref "BAT1") (pin "2") (pinfunction "2_2") (pintype "unspecified"))
      (node (ref "BAT1") (pin "4") (pinfunction "4_4") (pintype "unspecified"))
    )
    (net (code "45") (name "Net-(BAT1-Pad3)") (class "Default")
      (node (ref "BAT1") (pin "3") (pinfunction "3_3") (pintype "unspecified"))
      (node (ref "BAT1") (pin "5") (pinfunction "5_5") (pintype "unspecified"))
    )
    (net (code "46") (name "Net-(D1-K)") (class "Default")
      (node (ref "C7") (pin "2") (pinfunction "2_2") (pintype "input"))
      (node (ref "D1") (pin "2") (pinfunction "K_2") (pintype "unspecified"))
      (node (ref "L1") (pin "1") (pinfunction "1_1") (pintype "unspecified"))
      (node (ref "U14") (pin "8") (pinfunction "PH_8") (pintype "output"))
    )
    (net (code "47") (name "Net-(D2-A)") (class "Default")
      (node (ref "D2") (pin "1") (pinfunction "A_1") (pintype "unspecified"))
      (node (ref "L2") (pin "2") (pinfunction "2_2") (pintype "unspecified"))
      (node (ref "U31") (pin "1") (pinfunction "SW_1") (pintype "unspecified"))
    )
    (net (code "48") (name "Net-(LED1-A)") (class "Default")
      (node (ref "LED1") (pin "2") (pinfunction "A_2") (pintype "input"))
      (node (ref "R12") (pin "1") (pinfunction "1_1") (pintype "input"))
    )
    (net (code "49") (name "Net-(LED4-A)") (class "Default")
      (node (ref "LED4") (pin "2") (pinfunction "A_2") (pintype "input"))
      (node (ref "R9") (pin "1") (pinfunction "1_1") (pintype "input"))
    )
    (net (code "50") (name "Net-(LED5-C)") (class "Default")
      (node (ref "LED5") (pin "1") (pinfunction "C_1") (pintype "input"))
      (node (ref "LED7") (pin "1") (pinfunction "C_1") (pintype "input"))
      (node (ref "Q1") (pin "3") (pinfunction "C_3") (pintype "input"))
      (node (ref "R43") (pin "2") (pinfunction "2_2") (pintype "input"))
    )
    (net (code "51") (name "Net-(LED8-A)") (class "Default")
      (node (ref "LED8") (pin "2") (pinfunction "A_2") (pintype "input"))
      (node (ref "R45") (pin "1") (pinfunction "1_1") (pintype "input"))
    )
    (net (code "52") (name "Net-(Q1-B)") (class "Default")
      (node (ref "Q1") (pin "1") (pinfunction "B_1") (pintype "input"))
      (node (ref "R44") (pin "2") (pinfunction "2_2") (pintype "input"))
    )
    (net (code "53") (name "Net-(R36-Pad2)") (class "Default")
      (node (ref "R36") (pin "2") (pinfunction "2_2") (pintype "input"))
      (node (ref "SW3") (pin "1") (pinfunction "1_1") (pintype "input"))
    )
    (net (code "54") (name "Net-(R38-Pad1)") (class "Default")
      (node (ref "R38") (pin "1") (pinfunction "1_1") (pintype "input"))
      (node (ref "SW4") (pin "1") (pinfunction "1_1") (pintype "input"))
      (node (ref "SW5") (pin "2") (pinfunction "2_2") (pintype "input"))
    )
    (net (code "55") (name "Net-(U14-BOOT)") (class "Default")
      (node (ref "C7") (pin "1") (pinfunction "1_1") (pintype "input"))
      (node (ref "U14") (pin "1") (pinfunction "BOOT_1") (pintype "unspecified"))
    )
    (net (code "56") (name "Net-(U14-VIN)") (class "Default")
      (node (ref "C10") (pin "2") (pinfunction "2_2") (pintype "unspecified"))
      (node (ref "C11") (pin "2") (pinfunction "2_2") (pintype "unspecified"))
      (node (ref "C14") (pin "2") (pinfunction "2_2") (pintype "unspecified"))
      (node (ref "R9") (pin "2") (pinfunction "2_2") (pintype "input"))
      (node (ref "SW2") (pin "2") (pinfunction "2_2") (pintype "unspecified"))
      (node (ref "U14") (pin "7") (pinfunction "VIN_7") (pintype "input"))
    )
    (net (code "57") (name "Net-(U14-VSENSE)") (class "Default")
      (node (ref "R6") (pin "1") (pinfunction "1_1") (pintype "input"))
      (node (ref "R7") (pin "2") (pinfunction "2_2") (pintype "input"))
      (node (ref "U14") (pin "4") (pinfunction "VSENSE_4") (pintype "output"))
    )
    (net (code "58") (name "Net-(U31-FB)") (class "Default")
      (node (ref "R41") (pin "2") (pinfunction "2_2") (pintype "input"))
      (node (ref "R42") (pin "1") (pinfunction "1_1") (pintype "input"))
      (node (ref "U31") (pin "3") (pinfunction "FB_3") (pintype "unspecified"))
    )
    (net (code "59") (name "Net-(USB1-CC1)") (class "Default")
      (node (ref "R39") (pin "2") (pinfunction "2_2") (pintype "input"))
      (node (ref "USB1") (pin "A5") (pinfunction "CC1_A5") (pintype "unspecified"))
    )
    (net (code "60") (name "Net-(USB1-CC2)") (class "Default")
      (node (ref "R40") (pin "1") (pinfunction "1_1") (pintype "input"))
      (node (ref "USB1") (pin "B5") (pinfunction "CC2_B5") (pintype "unspecified"))
    )
    (net (code "61") (name "VCC") (class "Default")
      (node (ref "C38") (pin "2") (pinfunction "2_2") (pintype "input"))
      (node (ref "C39") (pin "2") (pinfunction "2_2") (pintype "input"))
      (node (ref "L2") (pin "1") (pinfunction "1_1") (pintype "unspecified"))
      (node (ref "U31") (pin "4") (pinfunction "EN_4") (pintype "unspecified"))
      (node (ref "U31") (pin "5") (pinfunction "VIN_5") (pintype "unspecified"))
      (node (ref "USB1") (pin "A9") (pinfunction "VBUS_A9") (pintype "unspecified"))
      (node (ref "USB1") (pin "B4") (pinfunction "VBUS_B4") (pintype "unspecified"))
    )
    (net (code "62") (name "VIN") (class "Default")
      (node (ref "BAT1") (pin "1") (pinfunction "1_1") (pintype "unspecified"))
      (node (ref "D3") (pin "1") (pinfunction "K_1") (pintype "unspecified"))
      (node (ref "R44") (pin "1") (pinfunction "1_1") (pintype "input"))
      (node (ref "SW2") (pin "3") (pinfunction "3_3") (pintype "unspecified"))
    )
    (net (code "63") (name "unconnected-(SW2-Pad1)") (class "Default")
      (node (ref "SW2") (pin "1") (pinfunction "1_1") (pintype "unspecified+no_connect"))
    )
    (net (code "64") (name "unconnected-(U14-ENA-Pad5)") (class "Default")
      (node (ref "U14") (pin "5") (pinfunction "ENA_5") (pintype "input+no_connect"))
    )
    (net (code "65") (name "unconnected-(U14-NC-Pad2)") (class "Default")
      (node (ref "U14") (pin "2") (pinfunction "NC_2") (pintype "unspecified+no_connect"))
    )
    (net (code "66") (name "unconnected-(U14-NC-Pad3)") (class "Default")
      (node (ref "U14") (pin "3") (pinfunction "NC_3") (pintype "unspecified+no_connect"))
    )
    (net (code "67") (name "unconnected-(U15-NC-Pad4)") (class "Default")
      (node (ref "U15") (pin "4") (pinfunction "NC_4") (pintype "unspecified+no_connect"))
    )
    (net (code "68") (name "unconnected-(U31-NC-Pad6)") (class "Default")
      (node (ref "U31") (pin "6") (pinfunction "NC_6") (pintype "unspecified+no_connect"))
    )
    (net (code "69") (name "unconnected-(U32-Pad5)") (class "Default")
      (node (ref "U32") (pin "5") (pinfunction "5_5") (pintype "unspecified"))
    )
    (net (code "70") (name "unconnected-(USB1-DN1-PadA7)") (class "Default")
      (node (ref "USB1") (pin "A7") (pinfunction "DN1_A7") (pintype "unspecified+no_connect"))
    )
    (net (code "71") (name "unconnected-(USB1-DN2-PadB7)") (class "Default")
      (node (ref "USB1") (pin "B7") (pinfunction "DN2_B7") (pintype "unspecified+no_connect"))
    )
    (net (code "72") (name "unconnected-(USB1-DP1-PadA6)") (class "Default")
      (node (ref "USB1") (pin "A6") (pinfunction "DP1_A6") (pintype "unspecified+no_connect"))
    )
    (net (code "73") (name "unconnected-(USB1-DP2-PadB6)") (class "Default")
      (node (ref "USB1") (pin "B6") (pinfunction "DP2_B6") (pintype "unspecified+no_connect"))
    )
    (net (code "74") (name "unconnected-(USB1-EP-Pad1)") (class "Default")
      (node (ref "USB1") (pin "1") (pinfunction "EP_1") (pintype "unspecified+no_connect"))
    )
    (net (code "75") (name "unconnected-(USB1-EP-Pad2)") (class "Default")
      (node (ref "USB1") (pin "2") (pinfunction "EP_2") (pintype "unspecified+no_connect"))
    )
    (net (code "76") (name "unconnected-(USB1-EP-Pad3)") (class "Default")
      (node (ref "USB1") (pin "3") (pinfunction "EP_3") (pintype "unspecified+no_connect"))
    )
    (net (code "77") (name "unconnected-(USB1-EP-Pad4)") (class "Default")
      (node (ref "USB1") (pin "4") (pinfunction "EP_4") (pintype "unspecified+no_connect"))
    )
    (net (code "78") (name "unconnected-(USB1-SSRXn1-PadB10)") (class "Default")
      (node (ref "USB1") (pin "B10") (pinfunction "SSRXn1_B10") (pintype "unspecified+no_connect"))
    )
    (net (code "79") (name "unconnected-(USB1-SSRXn2-PadA10)") (class "Default")
      (node (ref "USB1") (pin "A10") (pinfunction "SSRXn2_A10") (pintype "unspecified+no_connect"))
    )
    (net (code "80") (name "unconnected-(USB1-SSRXp1-PadB11)") (class "Default")
      (node (ref "USB1") (pin "B11") (pinfunction "SSRXp1_B11") (pintype "unspecified+no_connect"))
    )
    (net (code "81") (name "unconnected-(USB1-SSRXp2-PadA11)") (class "Default")
      (node (ref "USB1") (pin "A11") (pinfunction "SSRXp2_A11") (pintype "unspecified+no_connect"))
    )
    (net (code "82") (name "unconnected-(USB1-SSTXP1-PadA2)") (class "Default")
      (node (ref "USB1") (pin "A2") (pinfunction "SSTXP1_A2") (pintype "unspecified+no_connect"))
    )
    (net (code "83") (name "unconnected-(USB1-SSTXn1-PadA3)") (class "Default")
      (node (ref "USB1") (pin "A3") (pinfunction "SSTXn1_A3") (pintype "unspecified+no_connect"))
    )
    (net (code "84") (name "unconnected-(USB1-SSTXn2-PadB3)") (class "Default")
      (node (ref "USB1") (pin "B3") (pinfunction "SSTXn2_B3") (pintype "unspecified+no_connect"))
    )
    (net (code "85") (name "unconnected-(USB1-SSTXp2-PadB2)") (class "Default")
      (node (ref "USB1") (pin "B2") (pinfunction "SSTXp2_B2") (pintype "unspecified+no_connect"))
    )
    (net (code "86") (name "unconnected-(USB1-SUB1-PadA8)") (class "Default")
      (node (ref "USB1") (pin "A8") (pinfunction "SUB1_A8") (pintype "unspecified+no_connect"))
    )
    (net (code "87") (name "unconnected-(USB1-SUB2-PadB8)") (class "Default")
      (node (ref "USB1") (pin "B8") (pinfunction "SUB2_B8") (pintype "unspecified+no_connect"))
    )
    (net (code "88") (name "unconnected-(USB1-VBUS-PadA4)") (class "Default")
      (node (ref "USB1") (pin "A4") (pinfunction "VBUS_A4") (pintype "unspecified"))
    )
    (net (code "89") (name "unconnected-(USB1-VBUS-PadB9)") (class "Default")
      (node (ref "USB1") (pin "B9") (pinfunction "VBUS_B9") (pintype "unspecified"))
    )
  )
)
